# Power_and_connector.net
KiCad netlist of a schematic drawn in Altium Designer
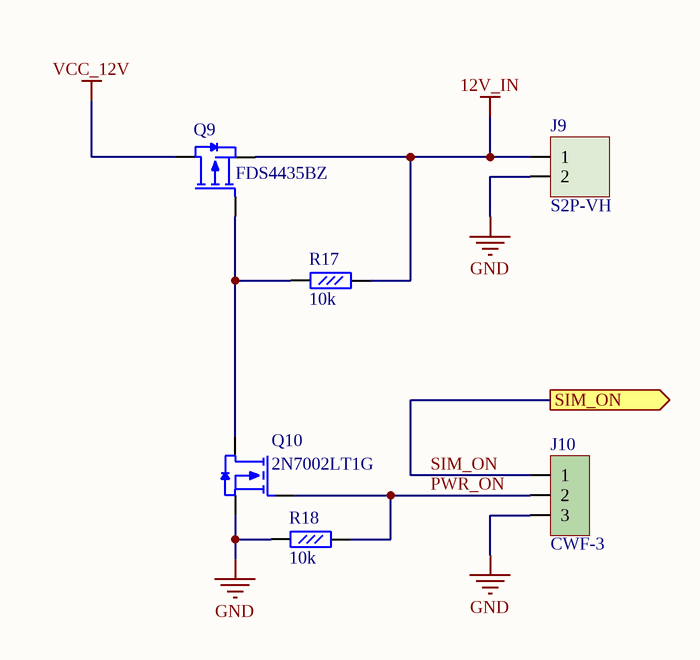
[diagram p0: Power_and_connector.SchDoc]

(export (version "E")
  (design (tool "Eeschema 10.0.6"))
  (components
    (comp (ref "J9")
      (value "S2P-VH")
      (footprint "PWL2-02R")
      (description "2-pin male header, pitch 3.96 mm")
      (fields (field (name "MANUFACTURER") "JST (China)") (field (name "Comment") "Разъём (вилка), S2P-VH"))
      (libsource (lib "Connectors") (part "B2P-VH"))
    )
    (comp (ref "J10")
      (value "CWF-3")
      (footprint "CWF-3")
      (description "3-pin male though-hole connector, pitch 2.5 mm")
      (fields (field (name "MANUFACTURER") "(China)") (field (name "PARTNUMBER") "CWF-3 (DS1069-3 M)"))
      (libsource (lib "Connectors") (part "CWF-3"))
    )
    (comp (ref "Q9")
      (value "Транзистор, FDS4435BZ")
      (footprint "SO-8")
      (description "P-Shannel 30 V 8A MOSFET")
      (fields (field (name "MANUFACTURER") "Fairchild") (field (name "PARTNUMBER") "FDS4435BZ"))
      (libsource (lib "Discrete") (part "FDS4435BZ"))
    )
    (comp (ref "Q10")
      (value "Транзистор, 2N7002LT1G")
      (footprint "SMD_components:SOT23")
      (description "N-channel OptiMOS™ Small-Signal-Transistor")
      (fields (field (name "MANUFACTURER") "Mnf") (field (name "PARTNUMBER") "2N7002LT1G"))
      (libsource (lib "Discrete") (part "2N7002"))
    )
    (comp (ref "R17")
      (value "10k")
      (footprint "SMD_components:R0603")
      (description "Chip Resistor 0603, 0.1 W")
      (fields (field (name "POWER") "0.1Вт") (field (name "TOLERANCE") "1%"))
      (libsource (lib "Passives") (part "R0603_0.1"))
    )
    (comp (ref "R18")
      (value "10k")
      (footprint "SMD_components:R0603")
      (description "Chip Resistor 0603, 0.1 W")
      (fields (field (name "POWER") "0.1Вт") (field (name "TOLERANCE") "1%"))
      (libsource (lib "Passives") (part "R0603_0.1"))
    )
  )
  (nets
    (net (code "1") (name "/PWR_ON") (class "Default")
      (node (ref "J10") (pin "2") (pinfunction "2_2") (pintype "passive"))
      (node (ref "Q10") (pin "1") (pinfunction "G_1") (pintype "passive"))
      (node (ref "R18") (pin "1") (pinfunction "1_1") (pintype "passive"))
    )
    (net (code "2") (name "/SIM_ON") (class "Default")
      (node (ref "J10") (pin "1") (pinfunction "1_1") (pintype "passive"))
    )
    (net (code "3") (name "12V_IN") (class "Default")
      (node (ref "J9") (pin "1") (pinfunction "1_1") (pintype "passive"))
      (node (ref "Q9") (pin "1") (pinfunction "S_1") (pintype "passive"))
      (node (ref "R17") (pin "1") (pinfunction "1_1") (pintype "passive"))
    )
    (net (code "4") (name "GND") (class "Default")
      (node (ref "J10") (pin "3") (pinfunction "3_3") (pintype "passive"))
      (node (ref "J9") (pin "2") (pinfunction "2_2") (pintype "passive"))
      (node (ref "Q10") (pin "2") (pinfunction "S_2") (pintype "passive"))
      (node (ref "R18") (pin "2") (pinfunction "2_2") (pintype "passive"))
    )
    (net (code "5") (name "Net-(Q10-D)") (class "Default")
      (node (ref "Q10") (pin "3") (pinfunction "D_3") (pintype "passive"))
      (node (ref "Q9") (pin "2") (pinfunction "G_2") (pintype "passive"))
      (node (ref "R17") (pin "2") (pinfunction "2_2") (pintype "passive"))
    )
    (net (code "6") (name "VCC_12V") (class "Default")
      (node (ref "Q9") (pin "3") (pinfunction "D_3") (pintype "passive"))
    )
  )
)
